# CANHub.net
KiCad netlist of a schematic drawn in Altium Designer
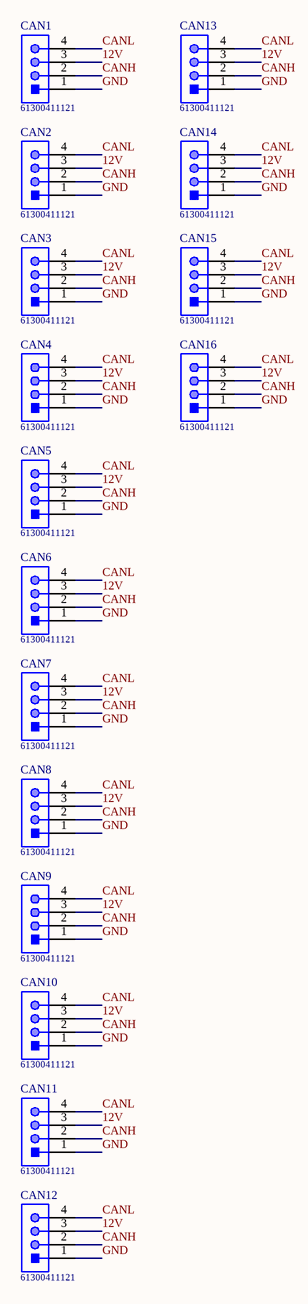
[diagram p0: CANHub.SchDoc]

(export (version "E")
  (design (tool "Eeschema 10.0.6"))
  (components
    (comp (ref "CAN1")
      (value "61300411121")
      (footprint "61300411121")
      (description "THT Vertical Pin Header WR-PHD, Pitch 2.54 mm, Single Row, 4 pins")
      (fields (field (name "MANUFACTURER") "Wurth Elektronik") (field (name "PUBLISHER") "WurthElektronik"))
      (libsource (lib "Altium Content Vault") (part "WE-CN-1P-M-R4"))
    )
    (comp (ref "CAN2")
      (value "61300411121")
      (footprint "61300411121")
      (description "THT Vertical Pin Header WR-PHD, Pitch 2.54 mm, Single Row, 4 pins")
      (fields (field (name "MANUFACTURER") "Wurth Elektronik") (field (name "PUBLISHER") "WurthElektronik"))
      (libsource (lib "Altium Content Vault") (part "WE-CN-1P-M-R4"))
    )
    (comp (ref "CAN3")
      (value "61300411121")
      (footprint "61300411121")
      (description "THT Vertical Pin Header WR-PHD, Pitch 2.54 mm, Single Row, 4 pins")
      (fields (field (name "MANUFACTURER") "Wurth Elektronik") (field (name "PUBLISHER") "WurthElektronik"))
      (libsource (lib "Altium Content Vault") (part "WE-CN-1P-M-R4"))
    )
    (comp (ref "CAN4")
      (value "61300411121")
      (footprint "61300411121")
      (description "THT Vertical Pin Header WR-PHD, Pitch 2.54 mm, Single Row, 4 pins")
      (fields (field (name "MANUFACTURER") "Wurth Elektronik") (field (name "PUBLISHER") "WurthElektronik"))
      (libsource (lib "Altium Content Vault") (part "WE-CN-1P-M-R4"))
    )
    (comp (ref "CAN5")
      (value "61300411121")
      (footprint "61300411121")
      (description "THT Vertical Pin Header WR-PHD, Pitch 2.54 mm, Single Row, 4 pins")
      (fields (field (name "MANUFACTURER") "Wurth Elektronik") (field (name "PUBLISHER") "WurthElektronik"))
      (libsource (lib "Altium Content Vault") (part "WE-CN-1P-M-R4"))
    )
    (comp (ref "CAN6")
      (value "61300411121")
      (footprint "61300411121")
      (description "THT Vertical Pin Header WR-PHD, Pitch 2.54 mm, Single Row, 4 pins")
      (fields (field (name "MANUFACTURER") "Wurth Elektronik") (field (name "PUBLISHER") "WurthElektronik"))
      (libsource (lib "Altium Content Vault") (part "WE-CN-1P-M-R4"))
    )
    (comp (ref "CAN7")
      (value "61300411121")
      (footprint "61300411121")
      (description "THT Vertical Pin Header WR-PHD, Pitch 2.54 mm, Single Row, 4 pins")
      (fields (field (name "MANUFACTURER") "Wurth Elektronik") (field (name "PUBLISHER") "WurthElektronik"))
      (libsource (lib "Altium Content Vault") (part "WE-CN-1P-M-R4"))
    )
    (comp (ref "CAN8")
      (value "61300411121")
      (footprint "61300411121")
      (description "THT Vertical Pin Header WR-PHD, Pitch 2.54 mm, Single Row, 4 pins")
      (fields (field (name "MANUFACTURER") "Wurth Elektronik") (field (name "PUBLISHER") "WurthElektronik"))
      (libsource (lib "Altium Content Vault") (part "WE-CN-1P-M-R4"))
    )
    (comp (ref "CAN9")
      (value "61300411121")
      (footprint "61300411121")
      (description "THT Vertical Pin Header WR-PHD, Pitch 2.54 mm, Single Row, 4 pins")
      (fields (field (name "MANUFACTURER") "Wurth Elektronik") (field (name "PUBLISHER") "WurthElektronik"))
      (libsource (lib "Altium Content Vault") (part "WE-CN-1P-M-R4"))
    )
    (comp (ref "CAN10")
      (value "61300411121")
      (footprint "61300411121")
      (description "THT Vertical Pin Header WR-PHD, Pitch 2.54 mm, Single Row, 4 pins")
      (fields (field (name "MANUFACTURER") "Wurth Elektronik") (field (name "PUBLISHER") "WurthElektronik"))
      (libsource (lib "Altium Content Vault") (part "WE-CN-1P-M-R4"))
    )
    (comp (ref "CAN11")
      (value "61300411121")
      (footprint "61300411121")
      (description "THT Vertical Pin Header WR-PHD, Pitch 2.54 mm, Single Row, 4 pins")
      (fields (field (name "MANUFACTURER") "Wurth Elektronik") (field (name "PUBLISHER") "WurthElektronik"))
      (libsource (lib "Altium Content Vault") (part "WE-CN-1P-M-R4"))
    )
    (comp (ref "CAN12")
      (value "61300411121")
      (footprint "61300411121")
      (description "THT Vertical Pin Header WR-PHD, Pitch 2.54 mm, Single Row, 4 pins")
      (fields (field (name "MANUFACTURER") "Wurth Elektronik") (field (name "PUBLISHER") "WurthElektronik"))
      (libsource (lib "Altium Content Vault") (part "WE-CN-1P-M-R4"))
    )
    (comp (ref "CAN13")
      (value "61300411121")
      (footprint "61300411121")
      (description "THT Vertical Pin Header WR-PHD, Pitch 2.54 mm, Single Row, 4 pins")
      (fields (field (name "MANUFACTURER") "Wurth Elektronik") (field (name "PUBLISHER") "WurthElektronik"))
      (libsource (lib "Altium Content Vault") (part "WE-CN-1P-M-R4"))
    )
    (comp (ref "CAN14")
      (value "61300411121")
      (footprint "61300411121")
      (description "THT Vertical Pin Header WR-PHD, Pitch 2.54 mm, Single Row, 4 pins")
      (fields (field (name "MANUFACTURER") "Wurth Elektronik") (field (name "PUBLISHER") "WurthElektronik"))
      (libsource (lib "Altium Content Vault") (part "WE-CN-1P-M-R4"))
    )
    (comp (ref "CAN15")
      (value "61300411121")
      (footprint "61300411121")
      (description "THT Vertical Pin Header WR-PHD, Pitch 2.54 mm, Single Row, 4 pins")
      (fields (field (name "MANUFACTURER") "Wurth Elektronik") (field (name "PUBLISHER") "WurthElektronik"))
      (libsource (lib "Altium Content Vault") (part "WE-CN-1P-M-R4"))
    )
    (comp (ref "CAN16")
      (value "61300411121")
      (footprint "61300411121")
      (description "THT Vertical Pin Header WR-PHD, Pitch 2.54 mm, Single Row, 4 pins")
      (fields (field (name "MANUFACTURER") "Wurth Elektronik") (field (name "PUBLISHER") "WurthElektronik"))
      (libsource (lib "Altium Content Vault") (part "WE-CN-1P-M-R4"))
    )
  )
  (nets
    (net (code "1") (name "/12V") (class "Default")
      (node (ref "CAN1") (pin "3") (pinfunction "3_3") (pintype "passive"))
      (node (ref "CAN10") (pin "3") (pinfunction "3_3") (pintype "passive"))
      (node (ref "CAN11") (pin "3") (pinfunction "3_3") (pintype "passive"))
      (node (ref "CAN12") (pin "3") (pinfunction "3_3") (pintype "passive"))
      (node (ref "CAN13") (pin "3") (pinfunction "3_3") (pintype "passive"))
      (node (ref "CAN14") (pin "3") (pinfunction "3_3") (pintype "passive"))
      (node (ref "CAN15") (pin "3") (pinfunction "3_3") (pintype "passive"))
      (node (ref "CAN16") (pin "3") (pinfunction "3_3") (pintype "passive"))
      (node (ref "CAN2") (pin "3") (pinfunction "3_3") (pintype "passive"))
      (node (ref "CAN3") (pin "3") (pinfunction "3_3") (pintype "passive"))
      (node (ref "CAN4") (pin "3") (pinfunction "3_3") (pintype "passive"))
      (node (ref "CAN5") (pin "3") (pinfunction "3_3") (pintype "passive"))
      (node (ref "CAN6") (pin "3") (pinfunction "3_3") (pintype "passive"))
      (node (ref "CAN7") (pin "3") (pinfunction "3_3") (pintype "passive"))
      (node (ref "CAN8") (pin "3") (pinfunction "3_3") (pintype "passive"))
      (node (ref "CAN9") (pin "3") (pinfunction "3_3") (pintype "passive"))
    )
    (net (code "2") (name "/CANH") (class "Default")
      (node (ref "CAN1") (pin "2") (pinfunction "2_2") (pintype "passive"))
      (node (ref "CAN10") (pin "2") (pinfunction "2_2") (pintype "passive"))
      (node (ref "CAN11") (pin "2") (pinfunction "2_2") (pintype "passive"))
      (node (ref "CAN12") (pin "2") (pinfunction "2_2") (pintype "passive"))
      (node (ref "CAN13") (pin "2") (pinfunction "2_2") (pintype "passive"))
      (node (ref "CAN14") (pin "2") (pinfunction "2_2") (pintype "passive"))
      (node (ref "CAN15") (pin "2") (pinfunction "2_2") (pintype "passive"))
      (node (ref "CAN16") (pin "2") (pinfunction "2_2") (pintype "passive"))
      (node (ref "CAN2") (pin "2") (pinfunction "2_2") (pintype "passive"))
      (node (ref "CAN3") (pin "2") (pinfunction "2_2") (pintype "passive"))
      (node (ref "CAN4") (pin "2") (pinfunction "2_2") (pintype "passive"))
      (node (ref "CAN5") (pin "2") (pinfunction "2_2") (pintype "passive"))
      (node (ref "CAN6") (pin "2") (pinfunction "2_2") (pintype "passive"))
      (node (ref "CAN7") (pin "2") (pinfunction "2_2") (pintype "passive"))
      (node (ref "CAN8") (pin "2") (pinfunction "2_2") (pintype "passive"))
      (node (ref "CAN9") (pin "2") (pinfunction "2_2") (pintype "passive"))
    )
    (net (code "3") (name "/CANL") (class "Default")
      (node (ref "CAN1") (pin "4") (pinfunction "4_4") (pintype "passive"))
      (node (ref "CAN10") (pin "4") (pinfunction "4_4") (pintype "passive"))
      (node (ref "CAN11") (pin "4") (pinfunction "4_4") (pintype "passive"))
      (node (ref "CAN12") (pin "4") (pinfunction "4_4") (pintype "passive"))
      (node (ref "CAN13") (pin "4") (pinfunction "4_4") (pintype "passive"))
      (node (ref "CAN14") (pin "4") (pinfunction "4_4") (pintype "passive"))
      (node (ref "CAN15") (pin "4") (pinfunction "4_4") (pintype "passive"))
      (node (ref "CAN16") (pin "4") (pinfunction "4_4") (pintype "passive"))
      (node (ref "CAN2") (pin "4") (pinfunction "4_4") (pintype "passive"))
      (node (ref "CAN3") (pin "4") (pinfunction "4_4") (pintype "passive"))
      (node (ref "CAN4") (pin "4") (pinfunction "4_4") (pintype "passive"))
      (node (ref "CAN5") (pin "4") (pinfunction "4_4") (pintype "passive"))
      (node (ref "CAN6") (pin "4") (pinfunction "4_4") (pintype "passive"))
      (node (ref "CAN7") (pin "4") (pinfunction "4_4") (pintype "passive"))
      (node (ref "CAN8") (pin "4") (pinfunction "4_4") (pintype "passive"))
      (node (ref "CAN9") (pin "4") (pinfunction "4_4") (pintype "passive"))
    )
    (net (code "4") (name "/GND") (class "Default")
      (node (ref "CAN1") (pin "1") (pinfunction "1_1") (pintype "passive"))
      (node (ref "CAN10") (pin "1") (pinfunction "1_1") (pintype "passive"))
      (node (ref "CAN11") (pin "1") (pinfunction "1_1") (pintype "passive"))
      (node (ref "CAN12") (pin "1") (pinfunction "1_1") (pintype "passive"))
      (node (ref "CAN13") (pin "1") (pinfunction "1_1") (pintype "passive"))
      (node (ref "CAN14") (pin "1") (pinfunction "1_1") (pintype "passive"))
      (node (ref "CAN15") (pin "1") (pinfunction "1_1") (pintype "passive"))
      (node (ref "CAN16") (pin "1") (pinfunction "1_1") (pintype "passive"))
      (node (ref "CAN2") (pin "1") (pinfunction "1_1") (pintype "passive"))
      (node (ref "CAN3") (pin "1") (pinfunction "1_1") (pintype "passive"))
      (node (ref "CAN4") (pin "1") (pinfunction "1_1") (pintype "passive"))
      (node (ref "CAN5") (pin "1") (pinfunction "1_1") (pintype "passive"))
      (node (ref "CAN6") (pin "1") (pinfunction "1_1") (pintype "passive"))
      (node (ref "CAN7") (pin "1") (pinfunction "1_1") (pintype "passive"))
      (node (ref "CAN8") (pin "1") (pinfunction "1_1") (pintype "passive"))
      (node (ref "CAN9") (pin "1") (pinfunction "1_1") (pintype "passive"))
    )
  )
)
